# aes4_to_6.net
KiCad netlist of a schematic drawn in EAGLE
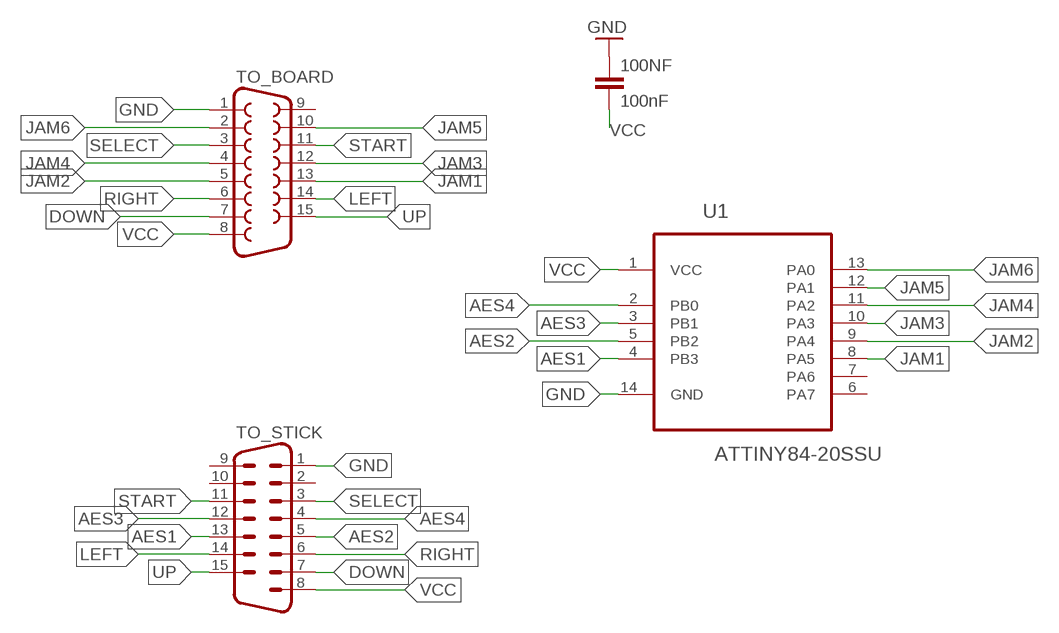
[diagram p0: schematic, sheet 1]

(export (version "E")
  (design (tool "Eeschema 10.0.6"))
  (components
    (comp (ref "100NF")
      (value "100nF")
      (footprint "eagle-import:0603")
      (libsource (lib "eagle-import") (part "10PF-0603-50V-5%"))
    )
    (comp (ref "TO_BOARD")
      (value "F15D")
      (footprint "eagle-import:F15D")
      (libsource (lib "eagle-import") (part "F15D"))
    )
    (comp (ref "TO_STICK")
      (value "M15D")
      (footprint "eagle-import:M15D")
      (libsource (lib "eagle-import") (part "M15D"))
    )
    (comp (ref "U1")
      (value "ATTINY84-20SSU")
      (footprint "eagle-import:SOIC127P600X175-14N")
      (libsource (lib "eagle-import") (part "ATTINY84-20SSU"))
    )
  )
  (nets
    (net (code "1") (name "AES1") (class "Default")
      (node (ref "TO_STICK") (pin "13") (pinfunction "13_13") (pintype "passive"))
      (node (ref "U1") (pin "4") (pinfunction "PB3_4") (pintype "bidirectional"))
    )
    (net (code "2") (name "AES2") (class "Default")
      (node (ref "TO_STICK") (pin "5") (pinfunction "5_5") (pintype "passive"))
      (node (ref "U1") (pin "5") (pinfunction "PB2_5") (pintype "bidirectional"))
    )
    (net (code "3") (name "AES3") (class "Default")
      (node (ref "TO_STICK") (pin "12") (pinfunction "12_12") (pintype "passive"))
      (node (ref "U1") (pin "3") (pinfunction "PB1_3") (pintype "bidirectional"))
    )
    (net (code "4") (name "AES4") (class "Default")
      (node (ref "TO_STICK") (pin "4") (pinfunction "4_4") (pintype "passive"))
      (node (ref "U1") (pin "2") (pinfunction "PB0_2") (pintype "bidirectional"))
    )
    (net (code "5") (name "DOWN") (class "Default")
      (node (ref "TO_BOARD") (pin "7") (pinfunction "7_7") (pintype "passive"))
      (node (ref "TO_STICK") (pin "7") (pinfunction "7_7") (pintype "passive"))
    )
    (net (code "6") (name "GND") (class "Default")
      (node (ref "100NF") (pin "1") (pinfunction "1_1") (pintype "passive"))
      (node (ref "TO_BOARD") (pin "1") (pinfunction "1_1") (pintype "passive"))
      (node (ref "TO_STICK") (pin "1") (pinfunction "1_1") (pintype "passive"))
      (node (ref "U1") (pin "14") (pinfunction "GND_14") (pintype "passive"))
    )
    (net (code "7") (name "JAM1") (class "Default")
      (node (ref "TO_BOARD") (pin "13") (pinfunction "13_13") (pintype "passive"))
      (node (ref "U1") (pin "8") (pinfunction "PA5_8") (pintype "bidirectional"))
    )
    (net (code "8") (name "JAM2") (class "Default")
      (node (ref "TO_BOARD") (pin "5") (pinfunction "5_5") (pintype "passive"))
      (node (ref "U1") (pin "9") (pinfunction "PA4_9") (pintype "bidirectional"))
    )
    (net (code "9") (name "JAM3") (class "Default")
      (node (ref "TO_BOARD") (pin "12") (pinfunction "12_12") (pintype "passive"))
      (node (ref "U1") (pin "10") (pinfunction "PA3_10") (pintype "bidirectional"))
    )
    (net (code "10") (name "JAM4") (class "Default")
      (node (ref "TO_BOARD") (pin "4") (pinfunction "4_4") (pintype "passive"))
      (node (ref "U1") (pin "11") (pinfunction "PA2_11") (pintype "bidirectional"))
    )
    (net (code "11") (name "JAM5") (class "Default")
      (node (ref "TO_BOARD") (pin "10") (pinfunction "10_10") (pintype "passive"))
      (node (ref "U1") (pin "12") (pinfunction "PA1_12") (pintype "bidirectional"))
    )
    (net (code "12") (name "JAM6") (class "Default")
      (node (ref "TO_BOARD") (pin "2") (pinfunction "2_2") (pintype "passive"))
      (node (ref "U1") (pin "13") (pinfunction "PA0_13") (pintype "bidirectional"))
    )
    (net (code "13") (name "LEFT") (class "Default")
      (node (ref "TO_BOARD") (pin "14") (pinfunction "14_14") (pintype "passive"))
      (node (ref "TO_STICK") (pin "14") (pinfunction "14_14") (pintype "passive"))
    )
    (net (code "14") (name "RIGHT") (class "Default")
      (node (ref "TO_BOARD") (pin "6") (pinfunction "6_6") (pintype "passive"))
      (node (ref "TO_STICK") (pin "6") (pinfunction "6_6") (pintype "passive"))
    )
    (net (code "15") (name "SELECT") (class "Default")
      (node (ref "TO_BOARD") (pin "3") (pinfunction "3_3") (pintype "passive"))
      (node (ref "TO_STICK") (pin "3") (pinfunction "3_3") (pintype "passive"))
    )
    (net (code "16") (name "START") (class "Default")
      (node (ref "TO_BOARD") (pin "11") (pinfunction "11_11") (pintype "passive"))
      (node (ref "TO_STICK") (pin "11") (pinfunction "11_11") (pintype "passive"))
    )
    (net (code "17") (name "UP") (class "Default")
      (node (ref "TO_BOARD") (pin "15") (pinfunction "15_15") (pintype "passive"))
      (node (ref "TO_STICK") (pin "15") (pinfunction "15_15") (pintype "passive"))
    )
    (net (code "18") (name "VCC") (class "Default")
      (node (ref "100NF") (pin "2") (pinfunction "2_2") (pintype "passive"))
      (node (ref "TO_BOARD") (pin "8") (pinfunction "8_8") (pintype "passive"))
      (node (ref "TO_STICK") (pin "8") (pinfunction "8_8") (pintype "passive"))
      (node (ref "U1") (pin "1") (pinfunction "VCC_1") (pintype "power_in"))
    )
    (net (code "19") (name "unconnected-(TO_BOARD-Pad9)") (class "Default")
      (node (ref "TO_BOARD") (pin "9") (pinfunction "9_9") (pintype "passive"))
    )
    (net (code "20") (name "unconnected-(TO_STICK-Pad2)") (class "Default")
      (node (ref "TO_STICK") (pin "2") (pinfunction "2_2") (pintype "passive"))
    )
    (net (code "21") (name "unconnected-(TO_STICK-Pad9)") (class "Default")
      (node (ref "TO_STICK") (pin "9") (pinfunction "9_9") (pintype "passive"))
    )
    (net (code "22") (name "unconnected-(TO_STICK-Pad10)") (class "Default")
      (node (ref "TO_STICK") (pin "10") (pinfunction "10_10") (pintype "passive"))
    )
    (net (code "23") (name "unconnected-(U1-PA6-Pad7)") (class "Default")
      (node (ref "U1") (pin "7") (pinfunction "PA6_7") (pintype "bidirectional"))
    )
    (net (code "24") (name "unconnected-(U1-PA7-Pad6)") (class "Default")
      (node (ref "U1") (pin "6") (pinfunction "PA7_6") (pintype "bidirectional"))
    )
  )
)
